# ST_LINK_V2-1_2.net
KiCad netlist of a schematic drawn in Altium Designer
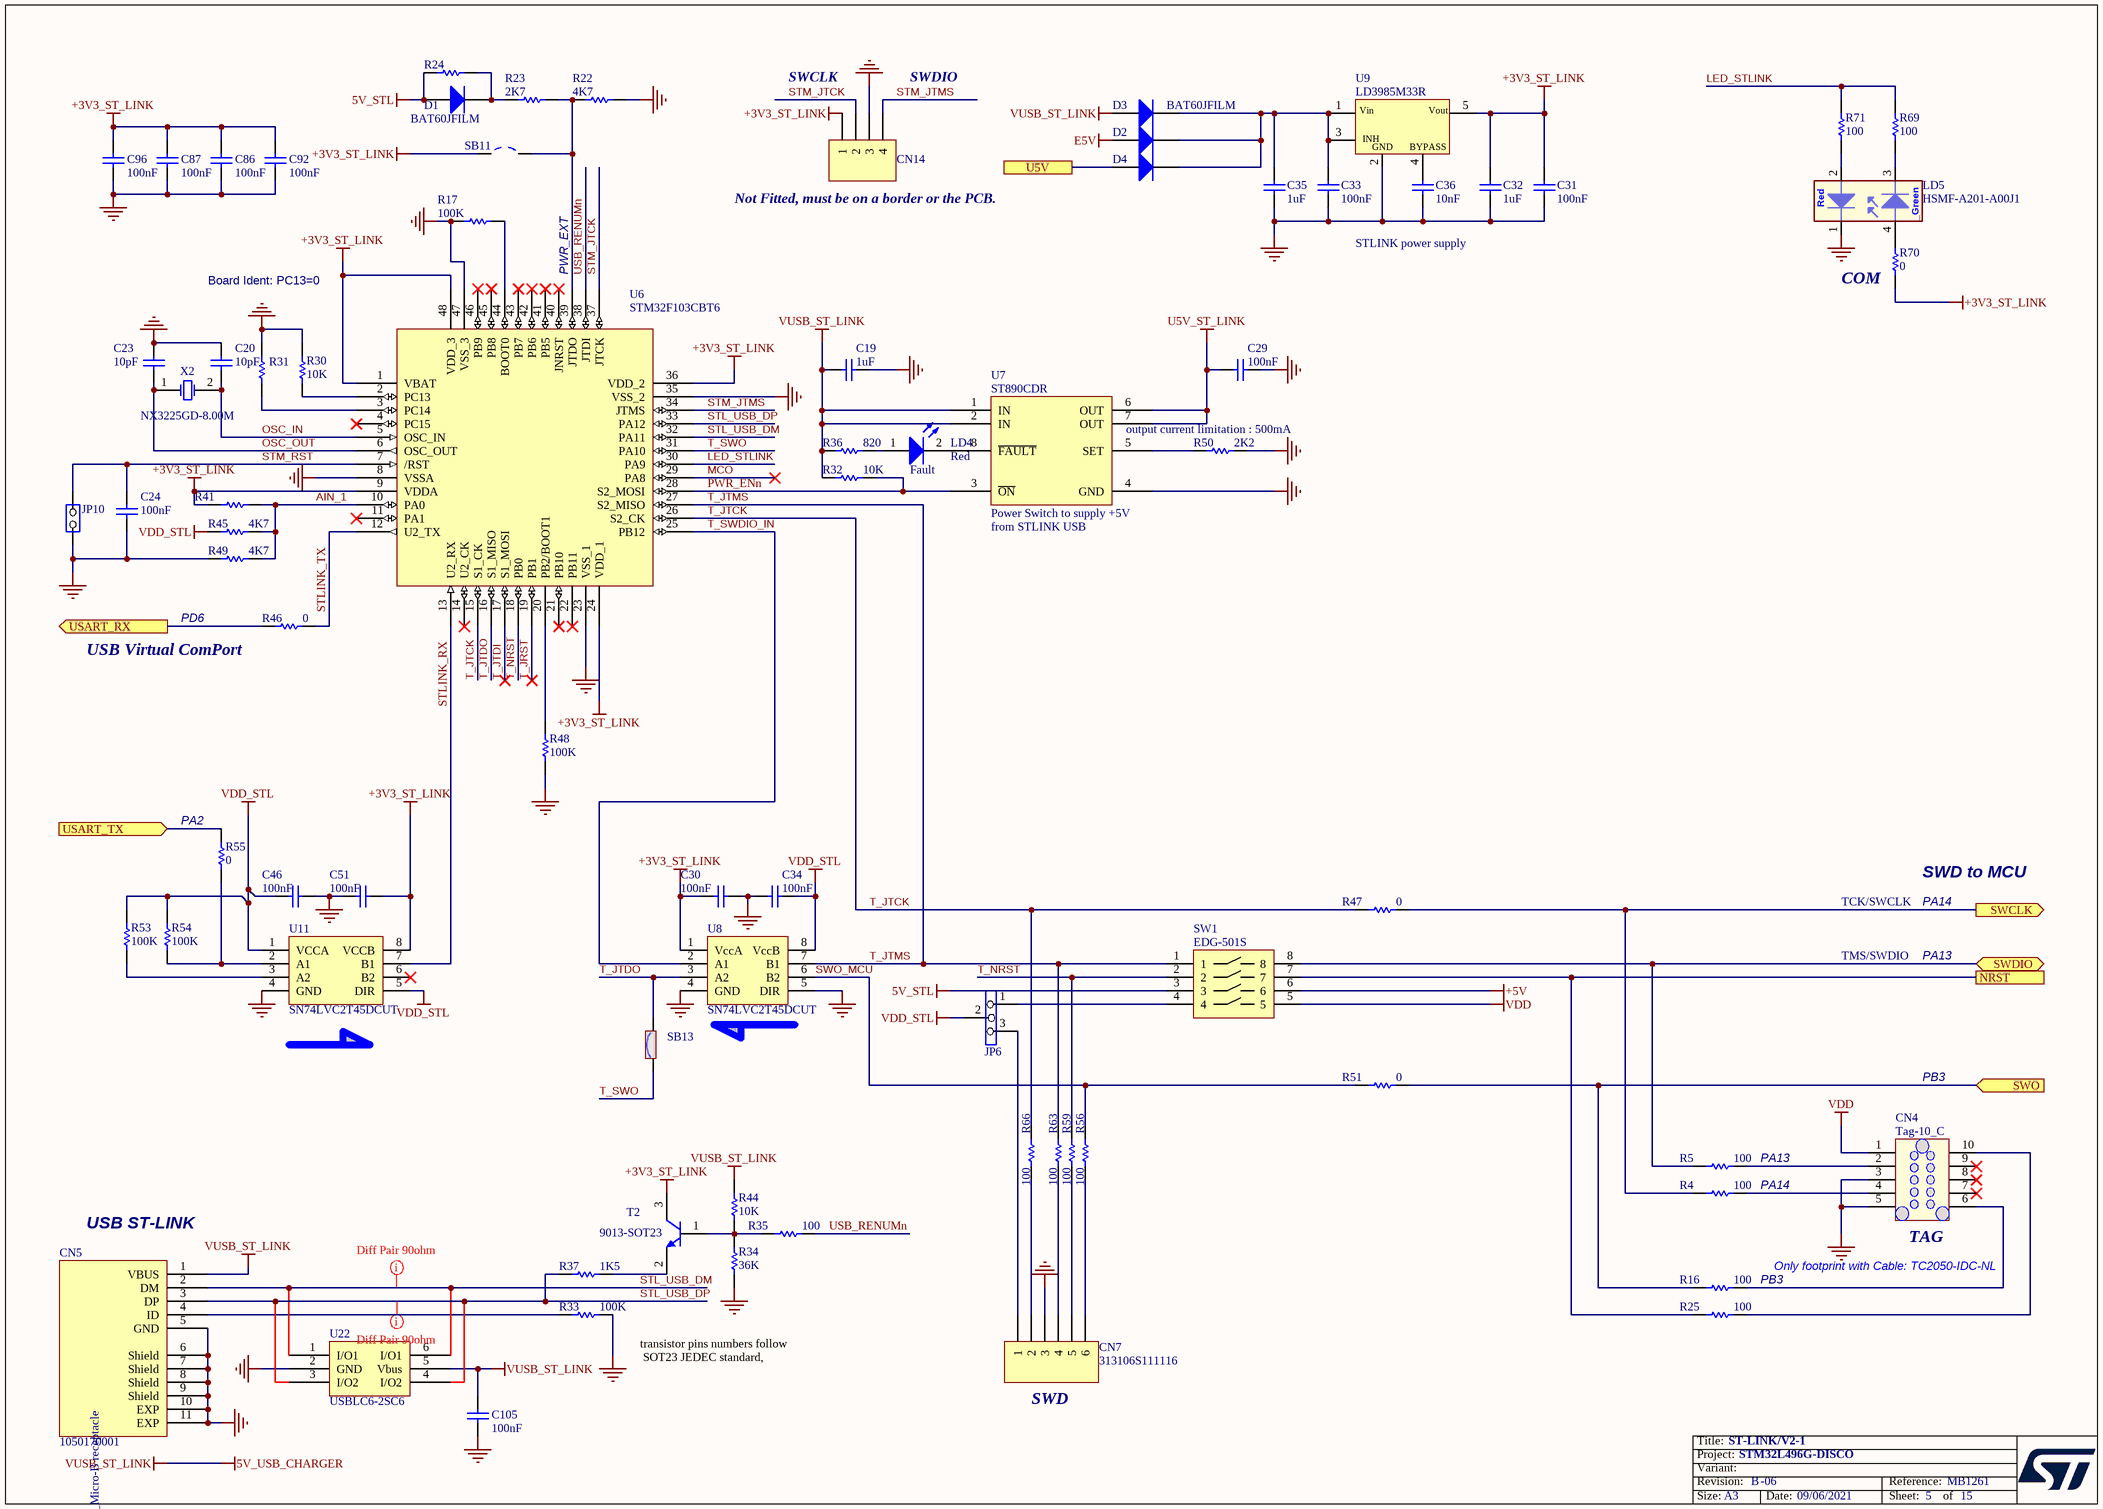
[diagram p0: ST_LINK_V2-1_2.SCHDOC]

(export (version "E")
  (design (tool "Eeschema 10.0.6"))
  (components
    (comp (ref "C19")
      (value "1uF")
      (footprint "0603C")
      (description "Capacitor,1uF,0603,16V,10%,X5R,YAGEO")
      (fields (field (name "Comment") "CC0603KRX5R7BB105") (field (name "PUBLISHER") "Altium Limited"))
      (libsource (lib "Miscellaneous Devices") (part "Cap"))
    )
    (comp (ref "C20")
      (value "10pF")
      (footprint "0603C")
      (description "Capacitor,10pF,5%,50V,NPO,0603,YAGEO")
      (fields (field (name "Comment") "CC0603JRNPO9BN100") (field (name "PUBLISHER") "Altium Limited"))
      (libsource (lib "Miscellaneous Devices") (part "Cap"))
    )
    (comp (ref "C23")
      (value "10pF")
      (footprint "0603C")
      (description "Capacitor,10pF,5%,50V,NPO,0603,YAGEO")
      (fields (field (name "Comment") "CC0603JRNPO9BN100") (field (name "PUBLISHER") "Altium Limited"))
      (libsource (lib "Miscellaneous Devices") (part "Cap"))
    )
    (comp (ref "C24")
      (value "100nF")
      (footprint "0603C")
      (description "Capacitor,100nF,10%,16V,X7R,0603,YAGEO")
      (fields (field (name "Comment") "CC0603KRX7R7BB104") (field (name "PUBLISHER") "Altium Limited"))
      (libsource (lib "Miscellaneous Devices") (part "Cap"))
    )
    (comp (ref "C29")
      (value "100nF")
      (footprint "0603C")
      (description "Capacitor,100nF,10%,16V,X7R,0603,YAGEO")
      (fields (field (name "Comment") "CC0603KRX7R7BB104") (field (name "PUBLISHER") "Altium Limited"))
      (libsource (lib "Miscellaneous Devices") (part "Cap"))
    )
    (comp (ref "C30")
      (value "100nF")
      (footprint "0603C")
      (description "Capacitor,100nF,10%,16V,X7R,0603,YAGEO")
      (fields (field (name "Comment") "CC0603KRX7R7BB104") (field (name "PUBLISHER") "Altium Limited"))
      (libsource (lib "Miscellaneous Devices") (part "Cap"))
    )
    (comp (ref "C31")
      (value "100nF")
      (footprint "0603C")
      (description "Capacitor,100nF,10%,16V,X7R,0603,YAGEO")
      (fields (field (name "Comment") "CC0603KRX7R7BB104") (field (name "PUBLISHER") "Altium Limited"))
      (libsource (lib "Miscellaneous Devices") (part "Cap"))
    )
    (comp (ref "C32")
      (value "1uF")
      (footprint "0603C")
      (description "Capacitor,1uF,0603,16V,10%,X5R,YAGEO")
      (fields (field (name "Comment") "CC0603KRX5R7BB105") (field (name "PUBLISHER") "Altium Limited"))
      (libsource (lib "Miscellaneous Devices") (part "Cap"))
    )
    (comp (ref "C33")
      (value "100nF")
      (footprint "0603C")
      (description "Capacitor,100nF,10%,16V,X7R,0603,YAGEO")
      (fields (field (name "Comment") "CC0603KRX7R7BB104") (field (name "PUBLISHER") "Altium Limited"))
      (libsource (lib "Miscellaneous Devices") (part "Cap"))
    )
    (comp (ref "C34")
      (value "100nF")
      (footprint "0603C")
      (description "Capacitor,100nF,10%,16V,X7R,0603,YAGEO")
      (fields (field (name "Comment") "CC0603KRX7R7BB104") (field (name "PUBLISHER") "Altium Limited"))
      (libsource (lib "Miscellaneous Devices") (part "Cap"))
    )
    (comp (ref "C35")
      (value "1uF")
      (footprint "0603C")
      (description "Capacitor,1uF,0603,16V,10%,X5R,YAGEO")
      (fields (field (name "Comment") "CC0603KRX5R7BB105") (field (name "PUBLISHER") "Altium Limited"))
      (libsource (lib "Miscellaneous Devices") (part "Cap"))
    )
    (comp (ref "C36")
      (value "10nF")
      (footprint "0603C")
      (description "Capacitor,10nF,0603,50V,10%,X7R,YAGEO;")
      (fields (field (name "Comment") "CC0603KRX7R9BB103") (field (name "PUBLISHER") "Altium Limited"))
      (libsource (lib "Miscellaneous Devices") (part "Cap"))
    )
    (comp (ref "C46")
      (value "100nF")
      (footprint "0603C")
      (description "Capacitor,100nF,10%,16V,X7R,0603,YAGEO")
      (fields (field (name "Comment") "CC0603KRX7R7BB104") (field (name "PUBLISHER") "Altium Limited"))
      (libsource (lib "Miscellaneous Devices") (part "Cap"))
    )
    (comp (ref "C51")
      (value "100nF")
      (footprint "0603C")
      (description "Capacitor,100nF,10%,16V,X7R,0603,YAGEO")
      (fields (field (name "Comment") "CC0603KRX7R7BB104") (field (name "PUBLISHER") "Altium Limited"))
      (libsource (lib "Miscellaneous Devices") (part "Cap"))
    )
    (comp (ref "C86")
      (value "100nF")
      (footprint "0603C")
      (description "Capacitor,100nF,10%,16V,X7R,0603,YAGEO")
      (fields (field (name "Comment") "CC0603KRX7R7BB104") (field (name "PUBLISHER") "Altium Limited"))
      (libsource (lib "Miscellaneous Devices") (part "Cap"))
    )
    (comp (ref "C87")
      (value "100nF")
      (footprint "0603C")
      (description "Capacitor,100nF,10%,16V,X7R,0603,YAGEO")
      (fields (field (name "Comment") "CC0603KRX7R7BB104") (field (name "PUBLISHER") "Altium Limited"))
      (libsource (lib "Miscellaneous Devices") (part "Cap"))
    )
    (comp (ref "C92")
      (value "100nF")
      (footprint "0603C")
      (description "Capacitor,100nF,10%,16V,X7R,0603,YAGEO")
      (fields (field (name "Comment") "CC0603KRX7R7BB104") (field (name "PUBLISHER") "Altium Limited"))
      (libsource (lib "Miscellaneous Devices") (part "Cap"))
    )
    (comp (ref "C96")
      (value "100nF")
      (footprint "0603C")
      (description "Capacitor,100nF,10%,16V,X7R,0603,YAGEO")
      (fields (field (name "Comment") "CC0603KRX7R7BB104") (field (name "PUBLISHER") "Altium Limited"))
      (libsource (lib "Miscellaneous Devices") (part "Cap"))
    )
    (comp (ref "C105")
      (value "100nF")
      (footprint "0603C")
      (description "Capacitor,100nF,10%,16V,X7R,0603,YAGEO")
      (fields (field (name "Comment") "CC0603KRX7R7BB104") (field (name "PUBLISHER") "Altium Limited"))
      (libsource (lib "Miscellaneous Devices") (part "Cap"))
    )
    (comp (ref "CN4")
      (value "Tag-10_C")
      (footprint "TC2050-IDC-NL")
      (description "Footprint for TC2050-IDC-430 plug of nails (TM) cable for MP430")
      (libsource (lib "MCD_TOOLS_CONNECTOR") (part "Tag-10_C"))
    )
    (comp (ref "CN5")
      (value "1050170001")
      (footprint "MICRO_USB_B_105017")
      (libsource (lib "Smartphone_accessory") (part "1050170001"))
    )
    (comp (ref "CN7")
      (value "313106S111116")
      (footprint "HDR_1X6_2R54_W")
      (description "Header, 6-Pin")
      (fields (field (name "PUBLISHER") "Altium Limited"))
      (libsource (lib "Miscellaneous Connectors") (part "Header 6"))
    )
    (comp (ref "CN14")
      (value "~")
      (footprint "HDR_1X4_2R54")
      (description "Header, 4-Pin")
      (fields (field (name "PUBLISHER") "Altium Limited"))
      (libsource (lib "MCD_TOOLS_CONNECTOR") (part "Header 4"))
    )
    (comp (ref "D1")
      (value "BAT60JFILM")
      (footprint "SOD-323")
      (fields (field (name "PROVIDED") "STM"))
      (libsource (lib "MCD_TOOLS") (part "BAT60JFILM"))
    )
    (comp (ref "D2")
      (value "~")
      (footprint "SOD-323")
      (description "BAT60JFILM")
      (fields (field (name "PROVIDED") "STM"))
      (libsource (lib "MCD_TOOLS") (part "BAT60JFILM"))
    )
    (comp (ref "D3")
      (value "BAT60JFILM")
      (footprint "SOD-323")
      (fields (field (name "PROVIDED") "STM"))
      (libsource (lib "MCD_TOOLS") (part "BAT60JFILM"))
    )
    (comp (ref "D4")
      (value "~")
      (footprint "SOD-323")
      (description "BAT60JFILM")
      (fields (field (name "PROVIDED") "STM"))
      (libsource (lib "MCD_TOOLS") (part "BAT60JFILM"))
    )
    (comp (ref "JP6")
      (value "3 PIN Jumper")
      (footprint "SIP3")
      (libsource (lib "STR910_SCHLIB") (part "Jumper3"))
    )
    (comp (ref "JP10") (value "~") (footprint "SIP2") (libsource (lib "*") (part "JP2")))
    (comp (ref "LD4")
      (value "19-217/R6C-AL1M2VY/3T")
      (footprint "0603D")
      (description "LED, Red ,0603")
      (fields
        (field (name "SILKSCREEN") "Fault")
        (field (name "CORLOR") "Red")
        (field (name "PUBLISHER") "Altium Limited")
      )
      (libsource (lib "Miscellaneous Devices") (part "LED2"))
    )
    (comp (ref "LD5")
      (value "HSMF-A201-A00J1")
      (footprint "LED2_3528")
      (description "Bicolor Led")
      (libsource (lib "MCD_TOOLS") (part "LD_BICOLOR_CMS"))
    )
    (comp (ref "R4")
      (value "100")
      (footprint "0603R")
      (description "Resistor, 100 ,0603,1%,YAGEO")
      (fields (field (name "Comment") "RC0603JR-07100RL") (field (name "PUBLISHER") "Altium Limited"))
      (libsource (lib "Miscellaneous Devices") (part "res1"))
    )
    (comp (ref "R5")
      (value "100")
      (footprint "0603R")
      (description "Resistor, 100 ,0603,1%,YAGEO")
      (fields (field (name "Comment") "RC0603JR-07100RL") (field (name "PUBLISHER") "Altium Limited"))
      (libsource (lib "Miscellaneous Devices") (part "res1"))
    )
    (comp (ref "R16")
      (value "100")
      (footprint "0603R")
      (description "Resistor, 100 ,0603,1%,YAGEO")
      (fields (field (name "Comment") "RC0603JR-07100RL") (field (name "PUBLISHER") "Altium Limited"))
      (libsource (lib "Miscellaneous Devices") (part "res1"))
    )
    (comp (ref "R17")
      (value "100K")
      (footprint "0603R")
      (description "Resistor,100K,0603,1%,YAGEO")
      (fields (field (name "Comment") "RC0603FR-07100KL") (field (name "PUBLISHER") "Altium Limited"))
      (libsource (lib "Miscellaneous Devices") (part "res1"))
    )
    (comp (ref "R22")
      (value "4K7")
      (footprint "0603R")
      (description "Resistor,4.7K,0603,1%,YAGEO")
      (fields (field (name "Comment") "RC0603FR-074K7L") (field (name "PUBLISHER") "Altium Limited"))
      (libsource (lib "Miscellaneous Devices") (part "res1"))
    )
    (comp (ref "R23")
      (value "2K7")
      (footprint "0603R")
      (description "Resistor,2.7K,0603,1%,YAGEO")
      (fields (field (name "Comment") "RC0603FR-072K7L") (field (name "PUBLISHER") "Altium Limited"))
      (libsource (lib "Miscellaneous Devices") (part "res1"))
    )
    (comp (ref "R24")
      (value "~")
      (footprint "0603R")
      (description "Resistor,0,0603,5%,YAGEO")
      (libsource (lib "MCD_TOOLS") (part "Res_0_5%_0402"))
    )
    (comp (ref "R25")
      (value "100")
      (footprint "0603R")
      (description "Resistor, 100 ,0603,1%,YAGEO")
      (fields (field (name "Comment") "RC0603JR-07100RL") (field (name "PUBLISHER") "Altium Limited"))
      (libsource (lib "Miscellaneous Devices") (part "res1"))
    )
    (comp (ref "R30")
      (value "10K")
      (footprint "0603R")
      (description "Resistor,10K,0603,1%,YAGEO")
      (fields (field (name "Comment") "RC0603FR-0710KL") (field (name "PUBLISHER") "Altium Limited"))
      (libsource (lib "Miscellaneous Devices") (part "res1"))
    )
    (comp (ref "R31")
      (value "~")
      (footprint "0603R")
      (description "Resistor,100K,0603,1%,YAGEO")
      (fields (field (name "PUBLISHER") "Altium Limited"))
      (libsource (lib "Miscellaneous Devices") (part "res1"))
    )
    (comp (ref "R32")
      (value "10K")
      (footprint "0603R")
      (description "Resistor,10K,0603,1%,YAGEO")
      (fields (field (name "Comment") "RC0603FR-0710KL") (field (name "PUBLISHER") "Altium Limited"))
      (libsource (lib "Miscellaneous Devices") (part "res1"))
    )
    (comp (ref "R33")
      (value "100K")
      (footprint "0603R")
      (description "Resistor,100K,0603,1%,YAGEO")
      (fields (field (name "Comment") "RC0603FR-07100KL") (field (name "PUBLISHER") "Altium Limited"))
      (libsource (lib "Miscellaneous Devices") (part "res1"))
    )
    (comp (ref "R34")
      (value "36K")
      (footprint "0603R")
      (description "Resistor,36K,0603,1%,YAGEO")
      (fields (field (name "Comment") "RC0603FR-0736KL") (field (name "PUBLISHER") "Altium Limited"))
      (libsource (lib "Miscellaneous Devices") (part "res1"))
    )
    (comp (ref "R35")
      (value "100")
      (footprint "0603R")
      (description "Resistor, 100 ,0603,1%,YAGEO")
      (fields (field (name "Comment") "RC0603JR-07100RL") (field (name "PUBLISHER") "Altium Limited"))
      (libsource (lib "Miscellaneous Devices") (part "res1"))
    )
    (comp (ref "R36")
      (value "820")
      (footprint "0603R")
      (description "Resistor")
      (fields (field (name "PUBLISHER") "Altium Limited"))
      (libsource (lib "Miscellaneous Devices") (part "res1"))
    )
    (comp (ref "R37")
      (value "1K5")
      (footprint "0603R")
      (description "Resistor,1.5K,0603,1%,YAGEO")
      (fields (field (name "Comment") "RC0603FR-071K5L") (field (name "PUBLISHER") "Altium Limited"))
      (libsource (lib "Miscellaneous Devices") (part "res1"))
    )
    (comp (ref "R41")
      (value "~")
      (footprint "0603R")
      (description "Resistor,100K,0603,1%,YAGEO")
      (fields (field (name "PUBLISHER") "Altium Limited"))
      (libsource (lib "Miscellaneous Devices") (part "res1"))
    )
    (comp (ref "R44")
      (value "10K")
      (footprint "0603R")
      (description "Resistor,10K,0603,1%,YAGEO")
      (fields (field (name "Comment") "RC0603FR-0710KL") (field (name "PUBLISHER") "Altium Limited"))
      (libsource (lib "Miscellaneous Devices") (part "res1"))
    )
    (comp (ref "R45")
      (value "4K7")
      (footprint "0603R")
      (description "Resistor,4.7K,0603,1%,YAGEO")
      (fields (field (name "Comment") "RC0603FR-074K7L") (field (name "PUBLISHER") "Altium Limited"))
      (libsource (lib "Miscellaneous Devices") (part "res1"))
    )
    (comp (ref "R46")
      (value "0")
      (footprint "0603R")
      (description "Resistor, 0 ,0603,1%,YAGEO")
      (fields (field (name "Comment") "RC0603JR-070RL") (field (name "PUBLISHER") "Altium Limited"))
      (libsource (lib "Miscellaneous Devices") (part "res1"))
    )
    (comp (ref "R47")
      (value "0")
      (footprint "0603R")
      (description "Resistor, 0 ,0603,1%,YAGEO")
      (fields (field (name "Comment") "RC0603JR-070RL") (field (name "PUBLISHER") "Altium Limited"))
      (libsource (lib "Miscellaneous Devices") (part "res1"))
    )
    (comp (ref "R48")
      (value "100K")
      (footprint "0603R")
      (description "Resistor,100K,0603,1%,YAGEO")
      (fields (field (name "Comment") "RC0603FR-07100KL") (field (name "PUBLISHER") "Altium Limited"))
      (libsource (lib "Miscellaneous Devices") (part "res1"))
    )
    (comp (ref "R49")
      (value "4K7")
      (footprint "0603R")
      (description "Resistor,4.7K,0603,1%,YAGEO")
      (fields (field (name "Comment") "RC0603FR-074K7L") (field (name "PUBLISHER") "Altium Limited"))
      (libsource (lib "Miscellaneous Devices") (part "res1"))
    )
    (comp (ref "R50")
      (value "2K2")
      (footprint "0603R")
      (description "Resistor,2.2K,0603,1%,YAGEO")
      (fields (field (name "Comment") "RC0603FR-072K2L") (field (name "PUBLISHER") "Altium Limited"))
      (libsource (lib "Miscellaneous Devices") (part "res1"))
    )
    (comp (ref "R51")
      (value "0")
      (footprint "0603R")
      (description "Resistor, 0 ,0603,1%,YAGEO")
      (fields (field (name "Comment") "RC0603JR-070RL") (field (name "PUBLISHER") "Altium Limited"))
      (libsource (lib "Miscellaneous Devices") (part "res1"))
    )
    (comp (ref "R53")
      (value "100K")
      (footprint "0603R")
      (description "Resistor,100K,0603,1%,YAGEO")
      (fields (field (name "Comment") "RC0603FR-07100KL") (field (name "PUBLISHER") "Altium Limited"))
      (libsource (lib "Miscellaneous Devices") (part "res1"))
    )
    (comp (ref "R54")
      (value "100K")
      (footprint "0603R")
      (description "Resistor,100K,0603,1%,YAGEO")
      (fields (field (name "Comment") "RC0603FR-07100KL") (field (name "PUBLISHER") "Altium Limited"))
      (libsource (lib "Miscellaneous Devices") (part "res1"))
    )
    (comp (ref "R55")
      (value "0")
      (footprint "0603R")
      (description "Resistor, 0 ,0603,1%,YAGEO")
      (fields (field (name "Comment") "RC0603JR-070RL") (field (name "PUBLISHER") "Altium Limited"))
      (libsource (lib "Miscellaneous Devices") (part "res1"))
    )
    (comp (ref "R56")
      (value "100")
      (footprint "0603R")
      (description "Resistor, 100 ,0603,1%,YAGEO")
      (fields (field (name "Comment") "RC0603JR-07100RL") (field (name "PUBLISHER") "Altium Limited"))
      (libsource (lib "Miscellaneous Devices") (part "res1"))
    )
    (comp (ref "R59")
      (value "100")
      (footprint "0603R")
      (description "Resistor, 100 ,0603,1%,YAGEO")
      (fields (field (name "Comment") "RC0603JR-07100RL") (field (name "PUBLISHER") "Altium Limited"))
      (libsource (lib "Miscellaneous Devices") (part "res1"))
    )
    (comp (ref "R63")
      (value "100")
      (footprint "0603R")
      (description "Resistor, 100 ,0603,1%,YAGEO")
      (fields (field (name "Comment") "RC0603JR-07100RL") (field (name "PUBLISHER") "Altium Limited"))
      (libsource (lib "Miscellaneous Devices") (part "res1"))
    )
    (comp (ref "R66")
      (value "100")
      (footprint "0603R")
      (description "Resistor, 100 ,0603,1%,YAGEO")
      (fields (field (name "Comment") "RC0603JR-07100RL") (field (name "PUBLISHER") "Altium Limited"))
      (libsource (lib "Miscellaneous Devices") (part "res1"))
    )
    (comp (ref "R69")
      (value "100")
      (footprint "0603R")
      (description "Resistor, 100 ,0603,1%,YAGEO")
      (fields (field (name "Comment") "RC0603JR-07100RL") (field (name "PUBLISHER") "Altium Limited"))
      (libsource (lib "Miscellaneous Devices") (part "res1"))
    )
    (comp (ref "R70")
      (value "0")
      (footprint "0603R")
      (description "Resistor, 0 ,0603,1%,YAGEO")
      (fields (field (name "Comment") "RC0603JR-070RL") (field (name "PUBLISHER") "Altium Limited"))
      (libsource (lib "Miscellaneous Devices") (part "res1"))
    )
    (comp (ref "R71")
      (value "100")
      (footprint "0603R")
      (description "Resistor, 100 ,0603,1%,YAGEO")
      (fields (field (name "Comment") "RC0603JR-07100RL") (field (name "PUBLISHER") "Altium Limited"))
      (libsource (lib "Miscellaneous Devices") (part "res1"))
    )
    (comp (ref "SB11")
      (value "Solder Bridge OFF")
      (footprint "SB_0603")
      (libsource (lib "MCD_TOOLS") (part "SB_OFF"))
    )
    (comp (ref "SB13")
      (value "Solder Bridge ON")
      (footprint "SB_0603")
      (libsource (lib "MCD_TOOLS") (part "SB_ON"))
    )
    (comp (ref "SW1")
      (value "EDG-501S")
      (footprint "SW1_11R7X9R7-12R2X9R65-HDR_CPT")
      (description "Gold Plated Contacts,4PST,1x4 Switch")
      (libsource (lib "Big Orga") (part "EDG-501S"))
    )
    (comp (ref "T2")
      (value "9013-SOT23")
      (footprint "SOT-23")
      (description "NPN Bipolar Transistor")
      (fields (field (name "PUBLISHER") "Altium Limited"))
      (libsource (lib "MB1167") (part "NPN"))
    )
    (comp (ref "U6")
      (value "STM32F103CBT6")
      (footprint "LQFP48_0R5_9X9")
      (description "IC,STM32F103CBT6,LQFP-48")
      (libsource (lib "*") (part "STM32F10x(48pin)"))
    )
    (comp (ref "U7")
      (value "ST890CDR")
      (footprint "SOIC8_1R27_4R9X6")
      (libsource (lib "MB1219") (part "ST890CDR"))
    )
    (comp (ref "U8")
      (value "SN74LVC2T45DCUT")
      (footprint "USOP8_0R5_2X3R1")
      (libsource (lib "STLINK") (part "SN74LVC2T45DCUT"))
    )
    (comp (ref "U9")
      (value "LD3985M33R")
      (footprint "SOT23-5")
      (description "Ultra low drop-low noise BiCMOS voltage, regulators low ESR capacitors compatible")
      (fields (field (name "PROVIDED") "STM"))
      (libsource (lib "MCD_TOOLS") (part "LD3985M33R"))
    )
    (comp (ref "U11")
      (value "SN74LVC2T45DCUT")
      (footprint "USOP8_0R5_2X3R1")
      (libsource (lib "MB818") (part "SN74LVC2T45DCUT"))
    )
    (comp (ref "U22")
      (value "USBLC6-2SC6")
      (footprint "SOT23-6L")
      (libsource (lib "MB1137") (part "USBLC6-2SC6"))
    )
    (comp (ref "X2")
      (value "NX3225GD-8.00M")
      (footprint "XTAL_2SM_3R2X2R5")
      (description "Crystal 8Mhz, 8pF, -+50PPM, SMD")
      (libsource (lib "MCD_TOOLS") (part "XTAL_8M_NX3225GD"))
    )
  )
  (nets
    (net (code "1") (name "+3V3_ST_LINK") (class "Default")
      (node (ref "C30") (pin "2") (pinfunction "2_2") (pintype "passive"))
      (node (ref "C31") (pin "1") (pinfunction "1_1") (pintype "passive"))
      (node (ref "C32") (pin "1") (pinfunction "1_1") (pintype "passive"))
      (node (ref "C51") (pin "2") (pinfunction "2_2") (pintype "passive"))
      (node (ref "C86") (pin "1") (pinfunction "1_1") (pintype "passive"))
      (node (ref "C87") (pin "1") (pinfunction "1_1") (pintype "passive"))
      (node (ref "C92") (pin "1") (pinfunction "1_1") (pintype "passive"))
      (node (ref "C96") (pin "1") (pinfunction "1_1") (pintype "passive"))
      (node (ref "CN14") (pin "1") (pinfunction "1_1") (pintype "passive"))
      (node (ref "R41") (pin "1") (pinfunction "1_1") (pintype "passive"))
      (node (ref "R70") (pin "1") (pinfunction "1_1") (pintype "passive"))
      (node (ref "SB11") (pin "1") (pinfunction "1_1") (pintype "passive"))
      (node (ref "T2") (pin "3") (pinfunction "C_3") (pintype "passive"))
      (node (ref "U11") (pin "8") (pinfunction "VCCB_8") (pintype "passive"))
      (node (ref "U6") (pin "1") (pinfunction "VBAT_1") (pintype "power_in"))
      (node (ref "U6") (pin "24") (pinfunction "VDD_1_24") (pintype "power_in"))
      (node (ref "U6") (pin "36") (pinfunction "VDD_2_36") (pintype "power_in"))
      (node (ref "U6") (pin "48") (pinfunction "VDD_3_48") (pintype "power_in"))
      (node (ref "U6") (pin "9") (pinfunction "VDDA_9") (pintype "power_in"))
      (node (ref "U8") (pin "1") (pinfunction "VccA_1") (pintype "passive"))
      (node (ref "U9") (pin "5") (pinfunction "Vout_5") (pintype "passive"))
    )
    (net (code "2") (name "+5V") (class "Default")
      (node (ref "SW1") (pin "6") (pinfunction "6_6") (pintype "passive"))
    )
    (net (code "3") (name "/AIN_1") (class "Default")
      (node (ref "R41") (pin "2") (pinfunction "2_2") (pintype "passive"))
      (node (ref "R45") (pin "1") (pinfunction "1_1") (pintype "passive"))
      (node (ref "R49") (pin "1") (pinfunction "1_1") (pintype "passive"))
      (node (ref "U6") (pin "10") (pinfunction "PA0_10") (pintype "bidirectional"))
    )
    (net (code "4") (name "/LED_STLINK") (class "Default")
      (node (ref "R69") (pin "1") (pinfunction "1_1") (pintype "passive"))
      (node (ref "R71") (pin "1") (pinfunction "1_1") (pintype "passive"))
      (node (ref "U6") (pin "30") (pinfunction "PA9_30") (pintype "bidirectional"))
    )
    (net (code "5") (name "/MCO") (class "Default")
      (node (ref "U6") (pin "29") (pinfunction "PA8_29") (pintype "bidirectional+no_connect"))
    )
    (net (code "6") (name "/NRST") (class "Default")
      (node (ref "R25") (pin "2") (pinfunction "2_2") (pintype "passive"))
      (node (ref "SW1") (pin "7") (pinfunction "7_7") (pintype "passive"))
    )
    (net (code "7") (name "/OSC_IN") (class "Default")
      (node (ref "C20") (pin "2") (pinfunction "2_2") (pintype "passive"))
      (node (ref "U6") (pin "5") (pinfunction "OSC_IN_5") (pintype "input"))
      (node (ref "X2") (pin "2") (pinfunction "OSC2_2") (pintype "passive"))
    )
    (net (code "8") (name "/OSC_OUT") (class "Default")
      (node (ref "C23") (pin "2") (pinfunction "2_2") (pintype "passive"))
      (node (ref "U6") (pin "6") (pinfunction "OSC_OUT_6") (pintype "output"))
      (node (ref "X2") (pin "1") (pinfunction "OSC1_1") (pintype "passive"))
    )
    (net (code "9") (name "/PWR_ENn") (class "Default")
      (node (ref "R32") (pin "2") (pinfunction "2_2") (pintype "passive"))
      (node (ref "U6") (pin "28") (pinfunction "S2_MOSI_28") (pintype "bidirectional"))
      (node (ref "U7") (pin "3") (pinfunction "~{ON}_3") (pintype "passive"))
    )
    (net (code "10") (name "/STLINK_RX") (class "Default")
      (node (ref "U11") (pin "7") (pinfunction "B1_7") (pintype "passive"))
      (node (ref "U6") (pin "13") (pinfunction "U2_RX_13") (pintype "input"))
    )
    (net (code "11") (name "/STLINK_TX") (class "Default")
      (node (ref "R46") (pin "1") (pinfunction "1_1") (pintype "passive"))
      (node (ref "U6") (pin "12") (pinfunction "U2_TX_12") (pintype "output"))
    )
    (net (code "12") (name "/STL_USB_DM") (class "Default")
      (node (ref "CN5") (pin "2") (pinfunction "DM_2") (pintype "passive"))
      (node (ref "U22") (pin "1") (pinfunction "I/O1_1") (pintype "passive"))
      (node (ref "U22") (pin "6") (pinfunction "I/O1_6") (pintype "passive"))
      (node (ref "U6") (pin "32") (pinfunction "PA11_32") (pintype "bidirectional"))
    )
    (net (code "13") (name "/STL_USB_DP") (class "Default")
      (node (ref "CN5") (pin "3") (pinfunction "DP_3") (pintype "passive"))
      (node (ref "R37") (pin "2") (pinfunction "2_2") (pintype "passive"))
      (node (ref "U22") (pin "3") (pinfunction "I/O2_3") (pintype "passive"))
      (node (ref "U22") (pin "4") (pinfunction "I/O2_4") (pintype "passive"))
      (node (ref "U6") (pin "33") (pinfunction "PA12_33") (pintype "bidirectional"))
    )
    (net (code "14") (name "/STM_JTCK") (class "Default")
      (node (ref "CN14") (pin "2") (pinfunction "2_2") (pintype "passive"))
      (node (ref "U6") (pin "37") (pinfunction "JTCK_37") (pintype "bidirectional"))
    )
    (net (code "15") (name "/STM_JTMS") (class "Default")
      (node (ref "CN14") (pin "4") (pinfunction "4_4") (pintype "passive"))
      (node (ref "U6") (pin "34") (pinfunction "JTMS_34") (pintype "bidirectional"))
    )
    (net (code "16") (name "/STM_RST") (class "Default")
      (node (ref "C24") (pin "1") (pinfunction "1_1") (pintype "passive"))
      (node (ref "JP10") (pin "1") (pinfunction "COMMON_1") (pintype "passive"))
      (node (ref "U6") (pin "7") (pinfunction "/RST_7") (pintype "input"))
    )
    (net (code "17") (name "/SWCLK") (class "Default")
      (node (ref "R4") (pin "2") (pinfunction "2_2") (pintype "passive"))
      (node (ref "R47") (pin "1") (pinfunction "1_1") (pintype "passive"))
    )
    (net (code "18") (name "/SWDIO") (class "Default")
      (node (ref "R5") (pin "2") (pinfunction "2_2") (pintype "passive"))
      (node (ref "SW1") (pin "8") (pinfunction "8_8") (pintype "passive"))
    )
    (net (code "19") (name "/SWO") (class "Default")
      (node (ref "R16") (pin "2") (pinfunction "2_2") (pintype "passive"))
      (node (ref "R51") (pin "1") (pinfunction "1_1") (pintype "passive"))
    )
    (net (code "20") (name "/SWO_MCU") (class "Default")
      (node (ref "R51") (pin "2") (pinfunction "2_2") (pintype "passive"))
      (node (ref "R56") (pin "2") (pinfunction "2_2") (pintype "passive"))
      (node (ref "U8") (pin "6") (pinfunction "B2_6") (pintype "passive"))
    )
    (net (code "21") (name "/T_JRST") (class "Default")
      (node (ref "U6") (pin "19") (pinfunction "PB1_19") (pintype "bidirectional+no_connect"))
    )
    (net (code "22") (name "/T_JTCK") (class "Default")
      (node (ref "R47") (pin "2") (pinfunction "2_2") (pintype "passive"))
      (node (ref "R66") (pin "2") (pinfunction "2_2") (pintype "passive"))
      (node (ref "U6") (pin "15") (pinfunction "S1_CK_15") (pintype "bidirectional"))
      (node (ref "U6") (pin "26") (pinfunction "S2_CK_26") (pintype "bidirectional"))
    )
    (net (code "23") (name "/T_JTDI") (class "Default")
      (node (ref "U6") (pin "17") (pinfunction "S1_MOSI_17") (pintype "bidirectional+no_connect"))
    )
    (net (code "24") (name "/T_JTDO") (class "Default")
      (node (ref "SB13") (pin "2") (pinfunction "2_2") (pintype "passive"))
      (node (ref "U6") (pin "16") (pinfunction "S1_MISO_16") (pintype "bidirectional"))
      (node (ref "U8") (pin "3") (pinfunction "A2_3") (pintype "passive"))
    )
    (net (code "25") (name "/T_JTMS") (class "Default")
      (node (ref "R63") (pin "2") (pinfunction "2_2") (pintype "passive"))
      (node (ref "SW1") (pin "1") (pinfunction "1_1") (pintype "passive"))
      (node (ref "U6") (pin "27") (pinfunction "S2_MISO_27") (pintype "bidirectional"))
      (node (ref "U8") (pin "7") (pinfunction "B1_7") (pintype "passive"))
    )
    (net (code "26") (name "/T_NRST") (class "Default")
      (node (ref "R59") (pin "2") (pinfunction "2_2") (pintype "passive"))
      (node (ref "SW1") (pin "2") (pinfunction "2_2") (pintype "passive"))
      (node (ref "U6") (pin "18") (pinfunction "PB0_18") (pintype "bidirectional"))
    )
    (net (code "27") (name "/T_SWDIO_IN") (class "Default")
      (node (ref "U6") (pin "25") (pinfunction "PB12_25") (pintype "bidirectional"))
      (node (ref "U8") (pin "2") (pinfunction "A1_2") (pintype "passive"))
    )
    (net (code "28") (name "/T_SWO") (class "Default")
      (node (ref "SB13") (pin "1") (pinfunction "1_1") (pintype "passive"))
      (node (ref "U6") (pin "31") (pinfunction "PA10_31") (pintype "bidirectional"))
    )
    (net (code "29") (name "/U5V") (class "Default")
      (node (ref "D4") (pin "1") (pinfunction "A_1") (pintype "passive"))
    )
    (net (code "30") (name "/USART_RX") (class "Default")
      (node (ref "R46") (pin "2") (pinfunction "2_2") (pintype "passive"))
    )
    (net (code "31") (name "/USART_TX") (class "Default")
      (node (ref "R55") (pin "1") (pinfunction "1_1") (pintype "passive"))
    )
    (net (code "32") (name "/USB_RENUMn") (class "Default")
      (node (ref "R35") (pin "2") (pinfunction "2_2") (pintype "passive"))
      (node (ref "U6") (pin "38") (pinfunction "JTDI_38") (pintype "bidirectional"))
    )
    (net (code "33") (name "5V_STL") (class "Default")
      (node (ref "D1") (pin "1") (pinfunction "A_1") (pintype "passive"))
      (node (ref "R24") (pin "2") (pinfunction "2_2") (pintype "passive"))
      (node (ref "SW1") (pin "3") (pinfunction "3_3") (pintype "passive"))
    )
    (net (code "34") (name "5V_USB_CHARGER") (class "Default")
      (node (ref "C105") (pin "1") (pinfunction "1_1") (pintype "passive"))
      (node (ref "C19") (pin "2") (pinfunction "2_2") (pintype "passive"))
      (node (ref "CN5") (pin "1") (pinfunction "VBUS_1") (pintype "passive"))
      (node (ref "D3") (pin "1") (pinfunction "A_1") (pintype "passive"))
      (node (ref "R32") (pin "1") (pinfunction "1_1") (pintype "passive"))
      (node (ref "R36") (pin "2") (pinfunction "2_2") (pintype "passive"))
      (node (ref "R44") (pin "1") (pinfunction "1_1") (pintype "passive"))
      (node (ref "U22") (pin "5") (pinfunction "Vbus_5") (pintype "passive"))
      (node (ref "U7") (pin "1") (pinfunction "IN_1") (pintype "passive"))
      (node (ref "U7") (pin "2") (pinfunction "IN_2") (pintype "passive"))
    )
    (net (code "35") (name "E5V") (class "Default")
      (node (ref "D2") (pin "1") (pinfunction "A_1") (pintype "passive"))
    )
    (net (code "36") (name "GND") (class "Default")
      (node (ref "C105") (pin "2") (pinfunction "2_2") (pintype "passive"))
      (node (ref "C19") (pin "1") (pinfunction "1_1") (pintype "passive"))
      (node (ref "C20") (pin "1") (pinfunction "1_1") (pintype "passive"))
      (node (ref "C23") (pin "1") (pinfunction "1_1") (pintype "passive"))
      (node (ref "C24") (pin "2") (pinfunction "2_2") (pintype "passive"))
      (node (ref "C29") (pin "1") (pinfunction "1_1") (pintype "passive"))
      (node (ref "C30") (pin "1") (pinfunction "1_1") (pintype "passive"))
      (node (ref "C31") (pin "2") (pinfunction "2_2") (pintype "passive"))
      (node (ref "C32") (pin "2") (pinfunction "2_2") (pintype "passive"))
      (node (ref "C33") (pin "2") (pinfunction "2_2") (pintype "passive"))
      (node (ref "C34") (pin "2") (pinfunction "2_2") (pintype "passive"))
      (node (ref "C35") (pin "2") (pinfunction "2_2") (pintype "passive"))
      (node (ref "C36") (pin "2") (pinfunction "2_2") (pintype "passive"))
      (node (ref "C46") (pin "2") (pinfunction "2_2") (pintype "passive"))
      (node (ref "C51") (pin "1") (pinfunction "1_1") (pintype "passive"))
      (node (ref "C86") (pin "2") (pinfunction "2_2") (pintype "passive"))
      (node (ref "C87") (pin "2") (pinfunction "2_2") (pintype "passive"))
      (node (ref "C92") (pin "2") (pinfunction "2_2") (pintype "passive"))
      (node (ref "C96") (pin "2") (pinfunction "2_2") (pintype "passive"))
      (node (ref "CN14") (pin "3") (pinfunction "3_3") (pintype "passive"))
      (node (ref "CN4") (pin "3") (pinfunction "3_3") (pintype "passive"))
      (node (ref "CN4") (pin "5") (pinfunction "5_5") (pintype "passive"))
      (node (ref "CN5") (pin "10") (pinfunction "EXP_10") (pintype "passive"))
      (node (ref "CN5") (pin "11") (pinfunction "EXP_11") (pintype "passive"))
      (node (ref "CN5") (pin "5") (pinfunction "GND_5") (pintype "passive"))
      (node (ref "CN5") (pin "6") (pinfunction "Shield_6") (pintype "passive"))
      (node (ref "CN5") (pin "7") (pinfunction "Shield_7") (pintype "passive"))
      (node (ref "CN5") (pin "8") (pinfunction "Shield_8") (pintype "passive"))
      (node (ref "CN5") (pin "9") (pinfunction "Shield_9") (pintype "passive"))
      (node (ref "CN7") (pin "3") (pinfunction "3_3") (pintype "passive"))
      (node (ref "JP10") (pin "2") (pinfunction "NO_2") (pintype "passive"))
      (node (ref "LD5") (pin "1") (pinfunction "1_1") (pintype "passive"))
      (node (ref "R17") (pin "2") (pinfunction "2_2") (pintype "passive"))
      (node (ref "R22") (pin "1") (pinfunction "1_1") (pintype "passive"))
      (node (ref "R30") (pin "1") (pinfunction "1_1") (pintype "passive"))
      (node (ref "R31") (pin "1") (pinfunction "1_1") (pintype "passive"))
      (node (ref "R33") (pin "1") (pinfunction "1_1") (pintype "passive"))
      (node (ref "R34") (pin "2") (pinfunction "2_2") (pintype "passive"))
      (node (ref "R48") (pin "1") (pinfunction "1_1") (pintype "passive"))
      (node (ref "R49") (pin "2") (pinfunction "2_2") (pintype "passive"))
      (node (ref "R50") (pin "1") (pinfunction "1_1") (pintype "passive"))
      (node (ref "U11") (pin "4") (pinfunction "GND_4") (pintype "passive"))
      (node (ref "U22") (pin "2") (pinfunction "GND_2") (pintype "passive"))
      (node (ref "U6") (pin "23") (pinfunction "VSS_1_23") (pintype "passive"))
      (node (ref "U6") (pin "35") (pinfunction "VSS_2_35") (pintype "passive"))
      (node (ref "U6") (pin "47") (pinfunction "VSS_3_47") (pintype "passive"))
      (node (ref "U6") (pin "8") (pinfunction "VSSA_8") (pintype "passive"))
      (node (ref "U7") (pin "4") (pinfunction "GND_4") (pintype "passive"))
      (node (ref "U8") (pin "4") (pinfunction "GND_4") (pintype "passive"))
      (node (ref "U8") (pin "5") (pinfunction "DIR_5") (pintype "passive"))
      (node (ref "U9") (pin "2") (pinfunction "GND_2") (pintype "passive"))
    )
    (net (code "37") (name "Net-(CN4-Pad2)") (class "Default")
      (node (ref "CN4") (pin "2") (pinfunction "2_2") (pintype "passive"))
      (node (ref "R5") (pin "1") (pinfunction "1_1") (pintype "passive"))
    )
    (net (code "38") (name "Net-(CN4-Pad4)") (class "Default")
      (node (ref "CN4") (pin "4") (pinfunction "4_4") (pintype "passive"))
      (node (ref "R4") (pin "1") (pinfunction "1_1") (pintype "passive"))
    )
    (net (code "39") (name "Net-(CN4-Pad6)") (class "Default")
      (node (ref "CN4") (pin "6") (pinfunction "6_6") (pintype "passive"))
      (node (ref "R16") (pin "1") (pinfunction "1_1") (pintype "passive"))
    )
    (net (code "40") (name "Net-(CN4-Pad10)") (class "Default")
      (node (ref "CN4") (pin "10") (pinfunction "10_10") (pintype "passive"))
      (node (ref "R25") (pin "1") (pinfunction "1_1") (pintype "passive"))
    )
    (net (code "41") (name "Net-(CN5-ID)") (class "Default")
      (node (ref "CN5") (pin "4") (pinfunction "ID_4") (pintype "passive"))
      (node (ref "R33") (pin "2") (pinfunction "2_2") (pintype "passive"))
    )
    (net (code "42") (name "Net-(CN7-Pad1)") (class "Default")
      (node (ref "CN7") (pin "1") (pinfunction "1_1") (pintype "passive"))
      (node (ref "JP6") (pin "3") (pintype "passive"))
    )
    (net (code "43") (name "Net-(CN7-Pad2)") (class "Default")
      (node (ref "CN7") (pin "2") (pinfunction "2_2") (pintype "passive"))
      (node (ref "R66") (pin "1") (pinfunction "1_1") (pintype "passive"))
    )
    (net (code "44") (name "Net-(CN7-Pad4)") (class "Default")
      (node (ref "CN7") (pin "4") (pinfunction "4_4") (pintype "passive"))
      (node (ref "R63") (pin "1") (pinfunction "1_1") (pintype "passive"))
    )
    (net (code "45") (name "Net-(CN7-Pad5)") (class "Default")
      (node (ref "CN7") (pin "5") (pinfunction "5_5") (pintype "passive"))
      (node (ref "R59") (pin "1") (pinfunction "1_1") (pintype "passive"))
    )
    (net (code "46") (name "Net-(CN7-Pad6)") (class "Default")
      (node (ref "CN7") (pin "6") (pinfunction "6_6") (pintype "passive"))
      (node (ref "R56") (pin "1") (pinfunction "1_1") (pintype "passive"))
    )
    (net (code "47") (name "Net-(D1-K)") (class "Default")
      (node (ref "D1") (pin "2") (pinfunction "K_2") (pintype "passive"))
      (node (ref "R23") (pin "2") (pinfunction "2_2") (pintype "passive"))
      (node (ref "R24") (pin "1") (pinfunction "1_1") (pintype "passive"))
    )
    (net (code "48") (name "Net-(D2-K)") (class "Default")
      (node (ref "C33") (pin "1") (pinfunction "1_1") (pintype "passive"))
      (node (ref "C35") (pin "1") (pinfunction "1_1") (pintype "passive"))
      (node (ref "D2") (pin "2") (pinfunction "K_2") (pintype "passive"))
      (node (ref "D3") (pin "2") (pinfunction "K_2") (pintype "passive"))
      (node (ref "D4") (pin "2") (pinfunction "K_2") (pintype "passive"))
      (node (ref "U9") (pin "1") (pinfunction "Vin_1") (pintype "passive"))
      (node (ref "U9") (pin "3") (pinfunction "CE_3") (pintype "passive"))
    )
    (net (code "49") (name "Net-(JP6-Pad1)") (class "Default")
      (node (ref "JP6") (pin "1") (pintype "passive"))
      (node (ref "SW1") (pin "4") (pinfunction "4_4") (pintype "passive"))
    )
    (net (code "50") (name "Net-(LD4-A)") (class "Default")
      (node (ref "LD4") (pin "1") (pinfunction "A_1") (pintype "passive"))
      (node (ref "R36") (pin "1") (pinfunction "1_1") (pintype "passive"))
    )
    (net (code "51") (name "Net-(LD4-K)") (class "Default")
      (node (ref "LD4") (pin "2") (pinfunction "K_2") (pintype "passive"))
      (node (ref "U7") (pin "8") (pinfunction "~{FAULT}_8") (pintype "passive"))
    )
    (net (code "52") (name "Net-(LD5-Pad2)") (class "Default")
      (node (ref "LD5") (pin "2") (pinfunction "2_2") (pintype "passive"))
      (node (ref "R71") (pin "2") (pinfunction "2_2") (pintype "passive"))
    )
    (net (code "53") (name "Net-(LD5-Pad3)") (class "Default")
      (node (ref "LD5") (pin "3") (pinfunction "3_3") (pintype "passive"))
      (node (ref "R69") (pin "2") (pinfunction "2_2") (pintype "passive"))
    )
    (net (code "54") (name "Net-(LD5-Pad4)") (class "Default")
      (node (ref "LD5") (pin "4") (pinfunction "4_4") (pintype "passive"))
      (node (ref "R70") (pin "2") (pinfunction "2_2") (pintype "passive"))
    )
    (net (code "55") (name "Net-(T2-B)") (class "Default")
      (node (ref "R34") (pin "1") (pinfunction "1_1") (pintype "passive"))
      (node (ref "R35") (pin "1") (pinfunction "1_1") (pintype "passive"))
      (node (ref "R44") (pin "2") (pinfunction "2_2") (pintype "passive"))
      (node (ref "T2") (pin "1") (pinfunction "B_1") (pintype "passive"))
    )
    (net (code "56") (name "Net-(T2-E)") (class "Default")
      (node (ref "R37") (pin "1") (pinfunction "1_1") (pintype "passive"))
      (node (ref "T2") (pin "2") (pinfunction "E_2") (pintype "passive"))
    )
    (net (code "57") (name "Net-(U6-BOOT0)") (class "Default")
      (node (ref "R17") (pin "1") (pinfunction "1_1") (pintype "passive"))
      (node (ref "U6") (pin "44") (pinfunction "BOOT0_44") (pintype "bidirectional"))
    )
    (net (code "58") (name "Net-(U6-JTDO)") (class "Default")
      (node (ref "R22") (pin "2") (pinfunction "2_2") (pintype "passive"))
      (node (ref "R23") (pin "1") (pinfunction "1_1") (pintype "passive"))
      (node (ref "SB11") (pin "2") (pinfunction "2_2") (pintype "passive"))
      (node (ref "U6") (pin "39") (pinfunction "JTDO_39") (pintype "bidirectional"))
    )
    (net (code "59") (name "Net-(U6-PB2{slash}BOOT1)") (class "Default")
      (node (ref "R48") (pin "2") (pinfunction "2_2") (pintype "passive"))
      (node (ref "U6") (pin "20") (pinfunction "PB2/BOOT1_20") (pintype "passive"))
    )
    (net (code "60") (name "Net-(U6-PC13)") (class "Default")
      (node (ref "R30") (pin "2") (pinfunction "2_2") (pintype "passive"))
      (node (ref "U6") (pin "2") (pinfunction "PC13_2") (pintype "bidirectional"))
    )
    (net (code "61") (name "Net-(U6-PC14)") (class "Default")
      (node (ref "R31") (pin "2") (pinfunction "2_2") (pintype "passive"))
      (node (ref "U6") (pin "3") (pinfunction "PC14_3") (pintype "bidirectional"))
    )
    (net (code "62") (name "Net-(U7-SET)") (class "Default")
      (node (ref "R50") (pin "2") (pinfunction "2_2") (pintype "passive"))
      (node (ref "U7") (pin "5") (pinfunction "SET_5") (pintype "passive"))
    )
    (net (code "63") (name "Net-(U9-BYPASS)") (class "Default")
      (node (ref "C36") (pin "1") (pinfunction "1_1") (pintype "passive"))
      (node (ref "U9") (pin "4") (pinfunction "BYPASS_4") (pintype "passive"))
    )
    (net (code "64") (name "Net-(U11-A1)") (class "Default")
      (node (ref "R54") (pin "1") (pinfunction "1_1") (pintype "passive"))
      (node (ref "R55") (pin "2") (pinfunction "2_2") (pintype "passive"))
      (node (ref "U11") (pin "2") (pinfunction "A1_2") (pintype "passive"))
    )
    (net (code "65") (name "Net-(U11-A2)") (class "Default")
      (node (ref "R53") (pin "1") (pinfunction "1_1") (pintype "passive"))
      (node (ref "U11") (pin "3") (pinfunction "A2_3") (pintype "passive"))
    )
    (net (code "66") (name "U5V_ST_LINK") (class "Default")
      (node (ref "C29") (pin "2") (pinfunction "2_2") (pintype "passive"))
      (node (ref "U7") (pin "6") (pinfunction "OUT_6") (pintype "passive"))
      (node (ref "U7") (pin "7") (pinfunction "OUT_7") (pintype "passive"))
    )
    (net (code "67") (name "VDD") (class "Default")
      (node (ref "CN4") (pin "1") (pinfunction "1_1") (pintype "passive"))
      (node (ref "SW1") (pin "5") (pinfunction "5_5") (pintype "passive"))
    )
    (net (code "68") (name "VDD_STL") (class "Default")
      (node (ref "C34") (pin "1") (pinfunction "1_1") (pintype "passive"))
      (node (ref "C46") (pin "1") (pinfunction "1_1") (pintype "passive"))
      (node (ref "JP6") (pin "2") (pintype "passive"))
      (node (ref "R45") (pin "2") (pinfunction "2_2") (pintype "passive"))
      (node (ref "R53") (pin "2") (pinfunction "2_2") (pintype "passive"))
      (node (ref "R54") (pin "2") (pinfunction "2_2") (pintype "passive"))
      (node (ref "U11") (pin "1") (pinfunction "VCCA_1") (pintype "passive"))
      (node (ref "U11") (pin "5") (pinfunction "DIR_5") (pintype "passive"))
      (node (ref "U8") (pin "8") (pinfunction "VccB_8") (pintype "passive"))
    )
    (net (code "69") (name "unconnected-(CN4-Pad7)") (class "Default")
      (node (ref "CN4") (pin "7") (pinfunction "7_7") (pintype "passive+no_connect"))
    )
    (net (code "70") (name "unconnected-(CN4-Pad8)") (class "Default")
      (node (ref "CN4") (pin "8") (pinfunction "8_8") (pintype "passive+no_connect"))
    )
    (net (code "71") (name "unconnected-(CN4-Pad9)") (class "Default")
      (node (ref "CN4") (pin "9") (pinfunction "9_9") (pintype "passive+no_connect"))
    )
    (net (code "72") (name "unconnected-(U6-JNRST-Pad40)") (class "Default")
      (node (ref "U6") (pin "40") (pinfunction "JNRST_40") (pintype "bidirectional+no_connect"))
    )
    (net (code "73") (name "unconnected-(U6-PA1-Pad11)") (class "Default")
      (node (ref "U6") (pin "11") (pinfunction "PA1_11") (pintype "bidirectional+no_connect"))
    )
    (net (code "74") (name "unconnected-(U6-PB5-Pad41)") (class "Default")
      (node (ref "U6") (pin "41") (pinfunction "PB5_41") (pintype "bidirectional+no_connect"))
    )
    (net (code "75") (name "unconnected-(U6-PB6-Pad42)") (class "Default")
      (node (ref "U6") (pin "42") (pinfunction "PB6_42") (pintype "bidirectional+no_connect"))
    )
    (net (code "76") (name "unconnected-(U6-PB7-Pad43)") (class "Default")
      (node (ref "U6") (pin "43") (pinfunction "PB7_43") (pintype "bidirectional+no_connect"))
    )
    (net (code "77") (name "unconnected-(U6-PB8-Pad45)") (class "Default")
      (node (ref "U6") (pin "45") (pinfunction "PB8_45") (pintype "bidirectional+no_connect"))
    )
    (net (code "78") (name "unconnected-(U6-PB9-Pad46)") (class "Default")
      (node (ref "U6") (pin "46") (pinfunction "PB9_46") (pintype "bidirectional+no_connect"))
    )
    (net (code "79") (name "unconnected-(U6-PB10-Pad21)") (class "Default")
      (node (ref "U6") (pin "21") (pinfunction "PB10_21") (pintype "bidirectional+no_connect"))
    )
    (net (code "80") (name "unconnected-(U6-PB11-Pad22)") (class "Default")
      (node (ref "U6") (pin "22") (pinfunction "PB11_22") (pintype "passive+no_connect"))
    )
    (net (code "81") (name "unconnected-(U6-PC15-Pad4)") (class "Default")
      (node (ref "U6") (pin "4") (pinfunction "PC15_4") (pintype "bidirectional+no_connect"))
    )
    (net (code "82") (name "unconnected-(U6-U2_CK-Pad14)") (class "Default")
      (node (ref "U6") (pin "14") (pinfunction "U2_CK_14") (pintype "bidirectional+no_connect"))
    )
    (net (code "83") (name "unconnected-(U11-B2-Pad6)") (class "Default")
      (node (ref "U11") (pin "6") (pinfunction "B2_6") (pintype "passive+no_connect"))
    )
  )
)
